# NRF_Breakout.net
KiCad netlist of a schematic drawn in EAGLE
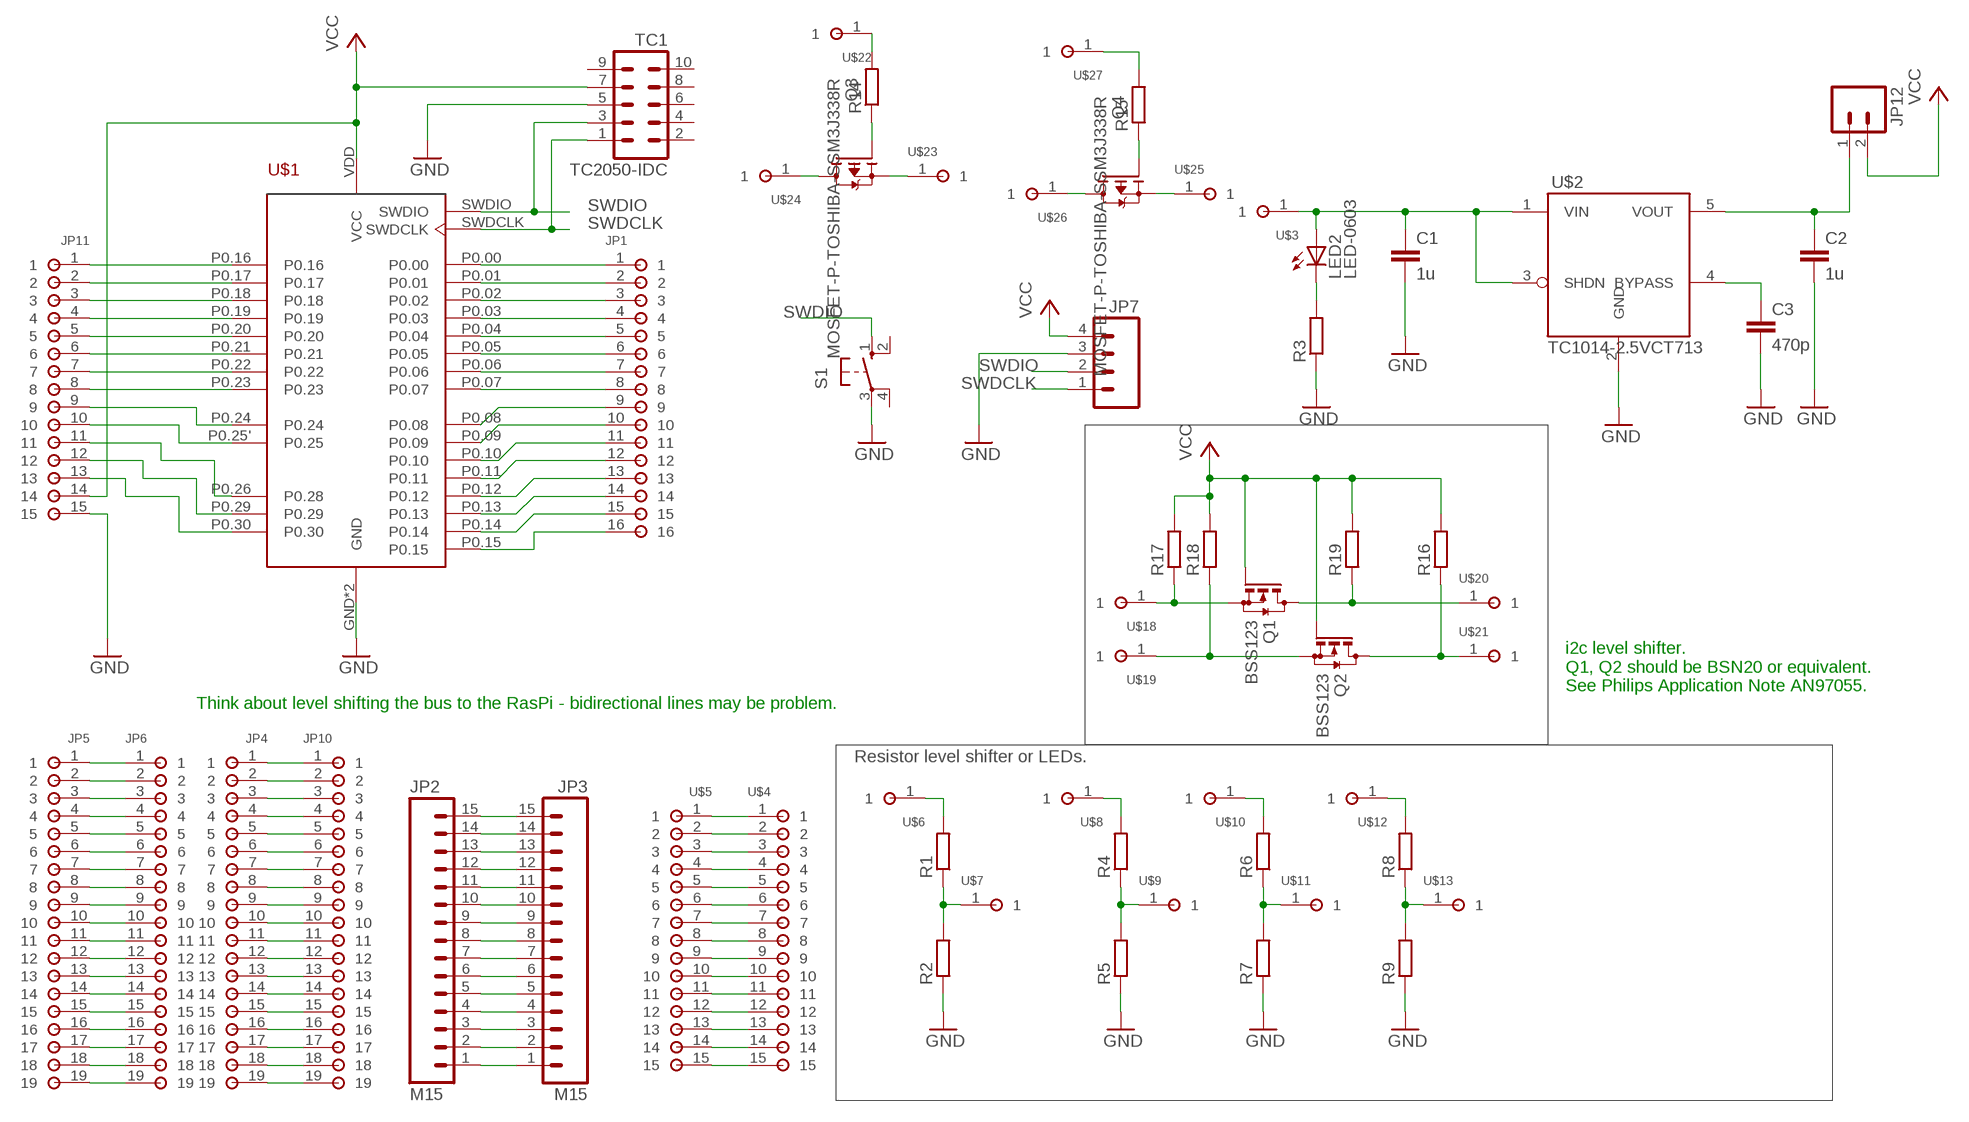
[diagram p0: schematic, sheet 1]

(export (version "E")
  (design (tool "Eeschema 10.0.6"))
  (components
    (comp (ref "C1")
      (value "1u")
      (footprint "eagle-import:C0603")
      (libsource (lib "eagle-import") (part "C-EUC0603"))
    )
    (comp (ref "C2")
      (value "1u")
      (footprint "eagle-import:C0603")
      (libsource (lib "eagle-import") (part "C-EUC0603"))
    )
    (comp (ref "C3")
      (value "470p")
      (footprint "eagle-import:C0603")
      (libsource (lib "eagle-import") (part "C-EUC0603"))
    )
    (comp (ref "JP1")
      (value "PAD-16-TH")
      (footprint "eagle-import:PAD-16-TH")
      (libsource (lib "eagle-import") (part "PAD-16-TH"))
    )
    (comp (ref "JP2")
      (value "M15")
      (footprint "eagle-import:1X15")
      (libsource (lib "eagle-import") (part "M15"))
    )
    (comp (ref "JP3")
      (value "M15")
      (footprint "eagle-import:1X15")
      (libsource (lib "eagle-import") (part "M15"))
    )
    (comp (ref "JP4")
      (value "PAD-19-2.54-TH")
      (footprint "eagle-import:PAD-19-2.54-TH")
      (libsource (lib "eagle-import") (part "PAD-19-2.54-TH"))
    )
    (comp (ref "JP5")
      (value "PAD-19-2.54-TH")
      (footprint "eagle-import:PAD-19-2.54-TH")
      (libsource (lib "eagle-import") (part "PAD-19-2.54-TH"))
    )
    (comp (ref "JP6")
      (value "PAD-19-2.54-TH")
      (footprint "eagle-import:PAD-19-2.54-TH")
      (libsource (lib "eagle-import") (part "PAD-19-2.54-TH"))
    )
    (comp (ref "JP7")
      (value "M04PTH")
      (footprint "eagle-import:1X04")
      (libsource (lib "eagle-import") (part "M04PTH"))
    )
    (comp (ref "JP10")
      (value "PAD-19-2.54-TH")
      (footprint "eagle-import:PAD-19-2.54-TH")
      (libsource (lib "eagle-import") (part "PAD-19-2.54-TH"))
    )
    (comp (ref "JP11")
      (value "PAD-15")
      (footprint "eagle-import:PAD-15-TH")
      (libsource (lib "eagle-import") (part "PAD-15"))
    )
    (comp (ref "JP12")
      (value "M02PTH")
      (footprint "eagle-import:1X02")
      (libsource (lib "eagle-import") (part "M02PTH"))
    )
    (comp (ref "LED2")
      (value "LED-0603")
      (footprint "eagle-import:CHIPLED_0603")
      (libsource (lib "eagle-import") (part "LED-0603"))
    )
    (comp (ref "Q1")
      (value "BSS123")
      (footprint "eagle-import:SOT23")
      (libsource (lib "eagle-import") (part "BSS123"))
    )
    (comp (ref "Q2")
      (value "BSS123")
      (footprint "eagle-import:SOT23")
      (libsource (lib "eagle-import") (part "BSS123"))
    )
    (comp (ref "Q3")
      (value "MOSFET-P-TOSHIBA-SSM3J338R")
      (footprint "eagle-import:SOT23")
      (libsource (lib "eagle-import") (part "MOSFET-P-TOSHIBA-SSM3J338R"))
    )
    (comp (ref "Q4")
      (value "MOSFET-P-TOSHIBA-SSM3J338R")
      (footprint "eagle-import:SOT23")
      (libsource (lib "eagle-import") (part "MOSFET-P-TOSHIBA-SSM3J338R"))
    )
    (comp (ref "R1")
      (value "R-EU_R0603")
      (footprint "eagle-import:R0603")
      (libsource (lib "eagle-import") (part "R-EU_R0603"))
    )
    (comp (ref "R2")
      (value "R-EU_R0603")
      (footprint "eagle-import:R0603")
      (libsource (lib "eagle-import") (part "R-EU_R0603"))
    )
    (comp (ref "R3")
      (value "R-EU_R0603")
      (footprint "eagle-import:R0603")
      (libsource (lib "eagle-import") (part "R-EU_R0603"))
    )
    (comp (ref "R4")
      (value "R-EU_R0603")
      (footprint "eagle-import:R0603")
      (libsource (lib "eagle-import") (part "R-EU_R0603"))
    )
    (comp (ref "R5")
      (value "R-EU_R0603")
      (footprint "eagle-import:R0603")
      (libsource (lib "eagle-import") (part "R-EU_R0603"))
    )
    (comp (ref "R6")
      (value "R-EU_R0603")
      (footprint "eagle-import:R0603")
      (libsource (lib "eagle-import") (part "R-EU_R0603"))
    )
    (comp (ref "R7")
      (value "R-EU_R0603")
      (footprint "eagle-import:R0603")
      (libsource (lib "eagle-import") (part "R-EU_R0603"))
    )
    (comp (ref "R8")
      (value "R-EU_R0603")
      (footprint "eagle-import:R0603")
      (libsource (lib "eagle-import") (part "R-EU_R0603"))
    )
    (comp (ref "R9")
      (value "R-EU_R0603")
      (footprint "eagle-import:R0603")
      (libsource (lib "eagle-import") (part "R-EU_R0603"))
    )
    (comp (ref "R14")
      (value "R-EU_R0603")
      (footprint "eagle-import:R0603")
      (libsource (lib "eagle-import") (part "R-EU_R0603"))
    )
    (comp (ref "R15")
      (value "R-EU_R0603")
      (footprint "eagle-import:R0603")
      (libsource (lib "eagle-import") (part "R-EU_R0603"))
    )
    (comp (ref "R16")
      (value "R-EU_R0603")
      (footprint "eagle-import:R0603")
      (libsource (lib "eagle-import") (part "R-EU_R0603"))
    )
    (comp (ref "R17")
      (value "R-EU_R0603")
      (footprint "eagle-import:R0603")
      (libsource (lib "eagle-import") (part "R-EU_R0603"))
    )
    (comp (ref "R18")
      (value "R-EU_R0603")
      (footprint "eagle-import:R0603")
      (libsource (lib "eagle-import") (part "R-EU_R0603"))
    )
    (comp (ref "R19")
      (value "R-EU_R0603")
      (footprint "eagle-import:R0603")
      (libsource (lib "eagle-import") (part "R-EU_R0603"))
    )
    (comp (ref "S1")
      (value "TACT-4PIN")
      (footprint "eagle-import:B3F-10XX")
      (fields (field (name "MPN") "B3F-1000"))
      (libsource (lib "eagle-import") (part "TACT-4PIN"))
    )
    (comp (ref "TC1")
      (value "TC2050-IDC")
      (footprint "eagle-import:TC2050-IDC")
      (libsource (lib "eagle-import") (part "TC2050-IDC"))
    )
    (comp (ref "U$1")
      (value "BREAKOUT-NRF51822CORE-SULLINS-NPPN092FFKS-RC")
      (footprint "eagle-import:BREAKOUT-NRF51822-CORE-SULLINS-NPPN092FFKS-RC")
      (libsource (lib "eagle-import") (part "BREAKOUT-NRF51822CORE-SULLINS-NPPN092FFKS-RC"))
    )
    (comp (ref "U$2")
      (value "TC1014-2.5VCT713")
      (footprint "eagle-import:SOT-23-5")
      (libsource (lib "eagle-import") (part "TC1014-2.5VCT713"))
    )
    (comp (ref "U$3")
      (value "PAD-1-TH")
      (footprint "eagle-import:PAD-1-TH")
      (libsource (lib "eagle-import") (part "PAD-1-TH"))
    )
    (comp (ref "U$4")
      (value "PAD-15")
      (footprint "eagle-import:PAD-15-TH")
      (libsource (lib "eagle-import") (part "PAD-15"))
    )
    (comp (ref "U$5")
      (value "PAD-15")
      (footprint "eagle-import:PAD-15-TH")
      (libsource (lib "eagle-import") (part "PAD-15"))
    )
    (comp (ref "U$6")
      (value "PAD-1-TH")
      (footprint "eagle-import:PAD-1-TH")
      (libsource (lib "eagle-import") (part "PAD-1-TH"))
    )
    (comp (ref "U$7")
      (value "PAD-1-TH")
      (footprint "eagle-import:PAD-1-TH")
      (libsource (lib "eagle-import") (part "PAD-1-TH"))
    )
    (comp (ref "U$8")
      (value "PAD-1-TH")
      (footprint "eagle-import:PAD-1-TH")
      (libsource (lib "eagle-import") (part "PAD-1-TH"))
    )
    (comp (ref "U$9")
      (value "PAD-1-TH")
      (footprint "eagle-import:PAD-1-TH")
      (libsource (lib "eagle-import") (part "PAD-1-TH"))
    )
    (comp (ref "U$10")
      (value "PAD-1-TH")
      (footprint "eagle-import:PAD-1-TH")
      (libsource (lib "eagle-import") (part "PAD-1-TH"))
    )
    (comp (ref "U$11")
      (value "PAD-1-TH")
      (footprint "eagle-import:PAD-1-TH")
      (libsource (lib "eagle-import") (part "PAD-1-TH"))
    )
    (comp (ref "U$12")
      (value "PAD-1-TH")
      (footprint "eagle-import:PAD-1-TH")
      (libsource (lib "eagle-import") (part "PAD-1-TH"))
    )
    (comp (ref "U$13")
      (value "PAD-1-TH")
      (footprint "eagle-import:PAD-1-TH")
      (libsource (lib "eagle-import") (part "PAD-1-TH"))
    )
    (comp (ref "U$18")
      (value "PAD-1-TH")
      (footprint "eagle-import:PAD-1-TH")
      (libsource (lib "eagle-import") (part "PAD-1-TH"))
    )
    (comp (ref "U$19")
      (value "PAD-1-TH")
      (footprint "eagle-import:PAD-1-TH")
      (libsource (lib "eagle-import") (part "PAD-1-TH"))
    )
    (comp (ref "U$20")
      (value "PAD-1-TH")
      (footprint "eagle-import:PAD-1-TH")
      (libsource (lib "eagle-import") (part "PAD-1-TH"))
    )
    (comp (ref "U$21")
      (value "PAD-1-TH")
      (footprint "eagle-import:PAD-1-TH")
      (libsource (lib "eagle-import") (part "PAD-1-TH"))
    )
    (comp (ref "U$22")
      (value "PAD-1-TH")
      (footprint "eagle-import:PAD-1-TH")
      (libsource (lib "eagle-import") (part "PAD-1-TH"))
    )
    (comp (ref "U$23")
      (value "PAD-1-TH")
      (footprint "eagle-import:PAD-1-TH")
      (libsource (lib "eagle-import") (part "PAD-1-TH"))
    )
    (comp (ref "U$24")
      (value "PAD-1-TH")
      (footprint "eagle-import:PAD-1-TH")
      (libsource (lib "eagle-import") (part "PAD-1-TH"))
    )
    (comp (ref "U$25")
      (value "PAD-1-TH")
      (footprint "eagle-import:PAD-1-TH")
      (libsource (lib "eagle-import") (part "PAD-1-TH"))
    )
    (comp (ref "U$26")
      (value "PAD-1-TH")
      (footprint "eagle-import:PAD-1-TH")
      (libsource (lib "eagle-import") (part "PAD-1-TH"))
    )
    (comp (ref "U$27")
      (value "PAD-1-TH")
      (footprint "eagle-import:PAD-1-TH")
      (libsource (lib "eagle-import") (part "PAD-1-TH"))
    )
  )
  (nets
    (net (code "1") (name "/SWDCLK") (class "Default")
      (node (ref "JP7") (pin "1") (pinfunction "1_1") (pintype "passive"))
      (node (ref "TC1") (pin "1") (pinfunction "1_1") (pintype "passive"))
      (node (ref "U$1") (pin "SWDCLK") (pinfunction "SWDCLK_SWDCLK") (pintype "bidirectional"))
    )
    (net (code "2") (name "/SWDIO") (class "Default")
      (node (ref "JP7") (pin "2") (pinfunction "2_2") (pintype "passive"))
      (node (ref "S1") (pin "1") (pinfunction "S_1") (pintype "passive"))
      (node (ref "TC1") (pin "3") (pinfunction "3_3") (pintype "passive"))
      (node (ref "U$1") (pin "SWDIO") (pinfunction "SWDIO_SWDIO") (pintype "bidirectional"))
    )
    (net (code "3") (name "GND") (class "Default")
      (node (ref "C1") (pin "2") (pinfunction "2_2") (pintype "passive"))
      (node (ref "C2") (pin "2") (pinfunction "2_2") (pintype "passive"))
      (node (ref "C3") (pin "2") (pinfunction "2_2") (pintype "passive"))
      (node (ref "JP11") (pin "15") (pinfunction "15_15") (pintype "bidirectional"))
      (node (ref "JP7") (pin "3") (pinfunction "3_3") (pintype "passive"))
      (node (ref "R2") (pin "1") (pinfunction "1_1") (pintype "passive"))
      (node (ref "R3") (pin "1") (pinfunction "1_1") (pintype "passive"))
      (node (ref "R5") (pin "1") (pinfunction "1_1") (pintype "passive"))
      (node (ref "R7") (pin "1") (pinfunction "1_1") (pintype "passive"))
      (node (ref "R9") (pin "1") (pinfunction "1_1") (pintype "passive"))
      (node (ref "S1") (pin "3") (pinfunction "P_3") (pintype "passive"))
      (node (ref "TC1") (pin "5") (pinfunction "5_5") (pintype "passive"))
      (node (ref "U$1") (pin "GND") (pinfunction "GND_GND") (pintype "bidirectional"))
      (node (ref "U$1") (pin "GND2") (pinfunction "GND_GND2") (pintype "bidirectional"))
      (node (ref "U$2") (pin "2") (pinfunction "GND_2") (pintype "power_in"))
    )
    (net (code "4") (name "Net-(JP1-Pad1)") (class "Default")
      (node (ref "JP1") (pin "1") (pinfunction "1_1") (pintype "bidirectional"))
      (node (ref "U$1") (pin "P0.00") (pinfunction "P0.00_P0.00") (pintype "bidirectional"))
    )
    (net (code "5") (name "Net-(JP1-Pad2)") (class "Default")
      (node (ref "JP1") (pin "2") (pinfunction "2_2") (pintype "bidirectional"))
      (node (ref "U$1") (pin "P0.01") (pinfunction "P0.01_P0.01") (pintype "bidirectional"))
    )
    (net (code "6") (name "Net-(JP1-Pad3)") (class "Default")
      (node (ref "JP1") (pin "3") (pinfunction "3_3") (pintype "bidirectional"))
      (node (ref "U$1") (pin "P0.02") (pinfunction "P0.02_P0.02") (pintype "bidirectional"))
    )
    (net (code "7") (name "Net-(JP1-Pad4)") (class "Default")
      (node (ref "JP1") (pin "4") (pinfunction "4_4") (pintype "bidirectional"))
      (node (ref "U$1") (pin "P0.03") (pinfunction "P0.03_P0.03") (pintype "bidirectional"))
    )
    (net (code "8") (name "Net-(JP1-Pad5)") (class "Default")
      (node (ref "JP1") (pin "5") (pinfunction "5_5") (pintype "bidirectional"))
      (node (ref "U$1") (pin "P0.04") (pinfunction "P0.04_P0.04") (pintype "bidirectional"))
    )
    (net (code "9") (name "Net-(JP1-Pad6)") (class "Default")
      (node (ref "JP1") (pin "6") (pinfunction "6_6") (pintype "bidirectional"))
      (node (ref "U$1") (pin "P0.05") (pinfunction "P0.05_P0.05") (pintype "bidirectional"))
    )
    (net (code "10") (name "Net-(JP1-Pad7)") (class "Default")
      (node (ref "JP1") (pin "7") (pinfunction "7_7") (pintype "bidirectional"))
      (node (ref "U$1") (pin "P0.06") (pinfunction "P0.06_P0.06") (pintype "bidirectional"))
    )
    (net (code "11") (name "Net-(JP1-Pad8)") (class "Default")
      (node (ref "JP1") (pin "8") (pinfunction "8_8") (pintype "bidirectional"))
      (node (ref "U$1") (pin "P0.07") (pinfunction "P0.07_P0.07") (pintype "bidirectional"))
    )
    (net (code "12") (name "Net-(JP1-Pad9)") (class "Default")
      (node (ref "JP1") (pin "9") (pinfunction "9_9") (pintype "bidirectional"))
      (node (ref "U$1") (pin "P0.08") (pinfunction "P0.08_P0.08") (pintype "bidirectional"))
    )
    (net (code "13") (name "Net-(JP1-Pad10)") (class "Default")
      (node (ref "JP1") (pin "10") (pinfunction "10_10") (pintype "bidirectional"))
      (node (ref "U$1") (pin "P0.09") (pinfunction "P0.09_P0.09") (pintype "bidirectional"))
    )
    (net (code "14") (name "Net-(JP1-Pad11)") (class "Default")
      (node (ref "JP1") (pin "11") (pinfunction "11_11") (pintype "bidirectional"))
      (node (ref "U$1") (pin "P0.10") (pinfunction "P0.10_P0.10") (pintype "bidirectional"))
    )
    (net (code "15") (name "Net-(JP1-Pad12)") (class "Default")
      (node (ref "JP1") (pin "12") (pinfunction "12_12") (pintype "bidirectional"))
      (node (ref "U$1") (pin "P0.11") (pinfunction "P0.11_P0.11") (pintype "bidirectional"))
    )
    (net (code "16") (name "Net-(JP1-Pad13)") (class "Default")
      (node (ref "JP1") (pin "13") (pinfunction "13_13") (pintype "bidirectional"))
      (node (ref "U$1") (pin "P0.12") (pinfunction "P0.12_P0.12") (pintype "bidirectional"))
    )
    (net (code "17") (name "Net-(JP1-Pad14)") (class "Default")
      (node (ref "JP1") (pin "14") (pinfunction "14_14") (pintype "bidirectional"))
      (node (ref "U$1") (pin "P0.13") (pinfunction "P0.13_P0.13") (pintype "bidirectional"))
    )
    (net (code "18") (name "Net-(JP1-Pad15)") (class "Default")
      (node (ref "JP1") (pin "15") (pinfunction "15_15") (pintype "bidirectional"))
      (node (ref "U$1") (pin "P0.14") (pinfunction "P0.14_P0.14") (pintype "bidirectional"))
    )
    (net (code "19") (name "Net-(JP1-Pad16)") (class "Default")
      (node (ref "JP1") (pin "16") (pinfunction "16_16") (pintype "bidirectional"))
      (node (ref "U$1") (pin "P0.15") (pinfunction "P0.15_P0.15") (pintype "bidirectional"))
    )
    (net (code "20") (name "Net-(JP2-Pad1)") (class "Default")
      (node (ref "JP2") (pin "1") (pinfunction "1_1") (pintype "passive"))
      (node (ref "JP3") (pin "1") (pinfunction "1_1") (pintype "passive"))
    )
    (net (code "21") (name "Net-(JP2-Pad2)") (class "Default")
      (node (ref "JP2") (pin "2") (pinfunction "2_2") (pintype "passive"))
      (node (ref "JP3") (pin "2") (pinfunction "2_2") (pintype "passive"))
    )
    (net (code "22") (name "Net-(JP2-Pad3)") (class "Default")
      (node (ref "JP2") (pin "3") (pinfunction "3_3") (pintype "passive"))
      (node (ref "JP3") (pin "3") (pinfunction "3_3") (pintype "passive"))
    )
    (net (code "23") (name "Net-(JP2-Pad4)") (class "Default")
      (node (ref "JP2") (pin "4") (pinfunction "4_4") (pintype "passive"))
      (node (ref "JP3") (pin "4") (pinfunction "4_4") (pintype "passive"))
    )
    (net (code "24") (name "Net-(JP2-Pad5)") (class "Default")
      (node (ref "JP2") (pin "5") (pinfunction "5_5") (pintype "passive"))
      (node (ref "JP3") (pin "5") (pinfunction "5_5") (pintype "passive"))
    )
    (net (code "25") (name "Net-(JP2-Pad6)") (class "Default")
      (node (ref "JP2") (pin "6") (pinfunction "6_6") (pintype "passive"))
      (node (ref "JP3") (pin "6") (pinfunction "6_6") (pintype "passive"))
    )
    (net (code "26") (name "Net-(JP2-Pad7)") (class "Default")
      (node (ref "JP2") (pin "7") (pinfunction "7_7") (pintype "passive"))
      (node (ref "JP3") (pin "7") (pinfunction "7_7") (pintype "passive"))
    )
    (net (code "27") (name "Net-(JP2-Pad8)") (class "Default")
      (node (ref "JP2") (pin "8") (pinfunction "8_8") (pintype "passive"))
      (node (ref "JP3") (pin "8") (pinfunction "8_8") (pintype "passive"))
    )
    (net (code "28") (name "Net-(JP2-Pad9)") (class "Default")
      (node (ref "JP2") (pin "9") (pinfunction "9_9") (pintype "passive"))
      (node (ref "JP3") (pin "9") (pinfunction "9_9") (pintype "passive"))
    )
    (net (code "29") (name "Net-(JP2-Pad10)") (class "Default")
      (node (ref "JP2") (pin "10") (pinfunction "10_10") (pintype "passive"))
      (node (ref "JP3") (pin "10") (pinfunction "10_10") (pintype "passive"))
    )
    (net (code "30") (name "Net-(JP2-Pad11)") (class "Default")
      (node (ref "JP2") (pin "11") (pinfunction "11_11") (pintype "passive"))
      (node (ref "JP3") (pin "11") (pinfunction "11_11") (pintype "passive"))
    )
    (net (code "31") (name "Net-(JP2-Pad12)") (class "Default")
      (node (ref "JP2") (pin "12") (pinfunction "12_12") (pintype "passive"))
      (node (ref "JP3") (pin "12") (pinfunction "12_12") (pintype "passive"))
    )
    (net (code "32") (name "Net-(JP2-Pad13)") (class "Default")
      (node (ref "JP2") (pin "13") (pinfunction "13_13") (pintype "passive"))
      (node (ref "JP3") (pin "13") (pinfunction "13_13") (pintype "passive"))
    )
    (net (code "33") (name "Net-(JP2-Pad14)") (class "Default")
      (node (ref "JP2") (pin "14") (pinfunction "14_14") (pintype "passive"))
      (node (ref "JP3") (pin "14") (pinfunction "14_14") (pintype "passive"))
    )
    (net (code "34") (name "Net-(JP2-Pad15)") (class "Default")
      (node (ref "JP2") (pin "15") (pinfunction "15_15") (pintype "passive"))
      (node (ref "JP3") (pin "15") (pinfunction "15_15") (pintype "passive"))
    )
    (net (code "35") (name "Net-(JP5-Pad1)") (class "Default")
      (node (ref "JP5") (pin "1") (pinfunction "1_1") (pintype "bidirectional"))
      (node (ref "JP6") (pin "1") (pinfunction "1_1") (pintype "bidirectional"))
    )
    (net (code "36") (name "Net-(JP5-Pad2)") (class "Default")
      (node (ref "JP5") (pin "2") (pinfunction "2_2") (pintype "bidirectional"))
      (node (ref "JP6") (pin "2") (pinfunction "2_2") (pintype "bidirectional"))
    )
    (net (code "37") (name "Net-(JP5-Pad3)") (class "Default")
      (node (ref "JP5") (pin "3") (pinfunction "3_3") (pintype "bidirectional"))
      (node (ref "JP6") (pin "3") (pinfunction "3_3") (pintype "bidirectional"))
    )
    (net (code "38") (name "Net-(JP5-Pad4)") (class "Default")
      (node (ref "JP5") (pin "4") (pinfunction "4_4") (pintype "bidirectional"))
      (node (ref "JP6") (pin "4") (pinfunction "4_4") (pintype "bidirectional"))
    )
    (net (code "39") (name "Net-(JP5-Pad5)") (class "Default")
      (node (ref "JP5") (pin "5") (pinfunction "5_5") (pintype "bidirectional"))
      (node (ref "JP6") (pin "5") (pinfunction "5_5") (pintype "bidirectional"))
    )
    (net (code "40") (name "Net-(JP5-Pad6)") (class "Default")
      (node (ref "JP5") (pin "6") (pinfunction "6_6") (pintype "bidirectional"))
      (node (ref "JP6") (pin "6") (pinfunction "6_6") (pintype "bidirectional"))
    )
    (net (code "41") (name "Net-(JP5-Pad7)") (class "Default")
      (node (ref "JP5") (pin "7") (pinfunction "7_7") (pintype "bidirectional"))
      (node (ref "JP6") (pin "7") (pinfunction "7_7") (pintype "bidirectional"))
    )
    (net (code "42") (name "Net-(JP5-Pad8)") (class "Default")
      (node (ref "JP5") (pin "8") (pinfunction "8_8") (pintype "bidirectional"))
      (node (ref "JP6") (pin "8") (pinfunction "8_8") (pintype "bidirectional"))
    )
    (net (code "43") (name "Net-(JP5-Pad9)") (class "Default")
      (node (ref "JP5") (pin "9") (pinfunction "9_9") (pintype "bidirectional"))
      (node (ref "JP6") (pin "9") (pinfunction "9_9") (pintype "bidirectional"))
    )
    (net (code "44") (name "Net-(JP5-Pad10)") (class "Default")
      (node (ref "JP5") (pin "10") (pinfunction "10_10") (pintype "bidirectional"))
      (node (ref "JP6") (pin "10") (pinfunction "10_10") (pintype "bidirectional"))
    )
    (net (code "45") (name "Net-(JP5-Pad11)") (class "Default")
      (node (ref "JP5") (pin "11") (pinfunction "11_11") (pintype "bidirectional"))
      (node (ref "JP6") (pin "11") (pinfunction "11_11") (pintype "bidirectional"))
    )
    (net (code "46") (name "Net-(JP5-Pad12)") (class "Default")
      (node (ref "JP5") (pin "12") (pinfunction "12_12") (pintype "bidirectional"))
      (node (ref "JP6") (pin "12") (pinfunction "12_12") (pintype "bidirectional"))
    )
    (net (code "47") (name "Net-(JP5-Pad13)") (class "Default")
      (node (ref "JP5") (pin "13") (pinfunction "13_13") (pintype "bidirectional"))
      (node (ref "JP6") (pin "13") (pinfunction "13_13") (pintype "bidirectional"))
    )
    (net (code "48") (name "Net-(JP5-Pad14)") (class "Default")
      (node (ref "JP5") (pin "14") (pinfunction "14_14") (pintype "bidirectional"))
      (node (ref "JP6") (pin "14") (pinfunction "14_14") (pintype "bidirectional"))
    )
    (net (code "49") (name "Net-(JP5-Pad15)") (class "Default")
      (node (ref "JP5") (pin "15") (pinfunction "15_15") (pintype "bidirectional"))
      (node (ref "JP6") (pin "15") (pinfunction "15_15") (pintype "bidirectional"))
    )
    (net (code "50") (name "Net-(JP5-Pad16)") (class "Default")
      (node (ref "JP5") (pin "16") (pinfunction "16_16") (pintype "bidirectional"))
      (node (ref "JP6") (pin "16") (pinfunction "16_16") (pintype "bidirectional"))
    )
    (net (code "51") (name "Net-(JP5-Pad17)") (class "Default")
      (node (ref "JP5") (pin "17") (pinfunction "17_17") (pintype "bidirectional"))
      (node (ref "JP6") (pin "17") (pinfunction "17_17") (pintype "bidirectional"))
    )
    (net (code "52") (name "Net-(JP5-Pad18)") (class "Default")
      (node (ref "JP5") (pin "18") (pinfunction "18_18") (pintype "bidirectional"))
      (node (ref "JP6") (pin "18") (pinfunction "18_18") (pintype "bidirectional"))
    )
    (net (code "53") (name "Net-(JP5-Pad19)") (class "Default")
      (node (ref "JP5") (pin "19") (pinfunction "19_19") (pintype "bidirectional"))
      (node (ref "JP6") (pin "19") (pinfunction "19_19") (pintype "bidirectional"))
    )
    (net (code "54") (name "Net-(JP10-Pad1)") (class "Default")
      (node (ref "JP10") (pin "1") (pinfunction "1_1") (pintype "bidirectional"))
      (node (ref "JP4") (pin "1") (pinfunction "1_1") (pintype "bidirectional"))
    )
    (net (code "55") (name "Net-(JP10-Pad2)") (class "Default")
      (node (ref "JP10") (pin "2") (pinfunction "2_2") (pintype "bidirectional"))
      (node (ref "JP4") (pin "2") (pinfunction "2_2") (pintype "bidirectional"))
    )
    (net (code "56") (name "Net-(JP10-Pad3)") (class "Default")
      (node (ref "JP10") (pin "3") (pinfunction "3_3") (pintype "bidirectional"))
      (node (ref "JP4") (pin "3") (pinfunction "3_3") (pintype "bidirectional"))
    )
    (net (code "57") (name "Net-(JP10-Pad4)") (class "Default")
      (node (ref "JP10") (pin "4") (pinfunction "4_4") (pintype "bidirectional"))
      (node (ref "JP4") (pin "4") (pinfunction "4_4") (pintype "bidirectional"))
    )
    (net (code "58") (name "Net-(JP10-Pad5)") (class "Default")
      (node (ref "JP10") (pin "5") (pinfunction "5_5") (pintype "bidirectional"))
      (node (ref "JP4") (pin "5") (pinfunction "5_5") (pintype "bidirectional"))
    )
    (net (code "59") (name "Net-(JP10-Pad6)") (class "Default")
      (node (ref "JP10") (pin "6") (pinfunction "6_6") (pintype "bidirectional"))
      (node (ref "JP4") (pin "6") (pinfunction "6_6") (pintype "bidirectional"))
    )
    (net (code "60") (name "Net-(JP10-Pad7)") (class "Default")
      (node (ref "JP10") (pin "7") (pinfunction "7_7") (pintype "bidirectional"))
      (node (ref "JP4") (pin "7") (pinfunction "7_7") (pintype "bidirectional"))
    )
    (net (code "61") (name "Net-(JP10-Pad8)") (class "Default")
      (node (ref "JP10") (pin "8") (pinfunction "8_8") (pintype "bidirectional"))
      (node (ref "JP4") (pin "8") (pinfunction "8_8") (pintype "bidirectional"))
    )
    (net (code "62") (name "Net-(JP10-Pad9)") (class "Default")
      (node (ref "JP10") (pin "9") (pinfunction "9_9") (pintype "bidirectional"))
      (node (ref "JP4") (pin "9") (pinfunction "9_9") (pintype "bidirectional"))
    )
    (net (code "63") (name "Net-(JP10-Pad10)") (class "Default")
      (node (ref "JP10") (pin "10") (pinfunction "10_10") (pintype "bidirectional"))
      (node (ref "JP4") (pin "10") (pinfunction "10_10") (pintype "bidirectional"))
    )
    (net (code "64") (name "Net-(JP10-Pad11)") (class "Default")
      (node (ref "JP10") (pin "11") (pinfunction "11_11") (pintype "bidirectional"))
      (node (ref "JP4") (pin "11") (pinfunction "11_11") (pintype "bidirectional"))
    )
    (net (code "65") (name "Net-(JP10-Pad12)") (class "Default")
      (node (ref "JP10") (pin "12") (pinfunction "12_12") (pintype "bidirectional"))
      (node (ref "JP4") (pin "12") (pinfunction "12_12") (pintype "bidirectional"))
    )
    (net (code "66") (name "Net-(JP10-Pad13)") (class "Default")
      (node (ref "JP10") (pin "13") (pinfunction "13_13") (pintype "bidirectional"))
      (node (ref "JP4") (pin "13") (pinfunction "13_13") (pintype "bidirectional"))
    )
    (net (code "67") (name "Net-(JP10-Pad14)") (class "Default")
      (node (ref "JP10") (pin "14") (pinfunction "14_14") (pintype "bidirectional"))
      (node (ref "JP4") (pin "14") (pinfunction "14_14") (pintype "bidirectional"))
    )
    (net (code "68") (name "Net-(JP10-Pad15)") (class "Default")
      (node (ref "JP10") (pin "15") (pinfunction "15_15") (pintype "bidirectional"))
      (node (ref "JP4") (pin "15") (pinfunction "15_15") (pintype "bidirectional"))
    )
    (net (code "69") (name "Net-(JP10-Pad16)") (class "Default")
      (node (ref "JP10") (pin "16") (pinfunction "16_16") (pintype "bidirectional"))
      (node (ref "JP4") (pin "16") (pinfunction "16_16") (pintype "bidirectional"))
    )
    (net (code "70") (name "Net-(JP10-Pad17)") (class "Default")
      (node (ref "JP10") (pin "17") (pinfunction "17_17") (pintype "bidirectional"))
      (node (ref "JP4") (pin "17") (pinfunction "17_17") (pintype "bidirectional"))
    )
    (net (code "71") (name "Net-(JP10-Pad18)") (class "Default")
      (node (ref "JP10") (pin "18") (pinfunction "18_18") (pintype "bidirectional"))
      (node (ref "JP4") (pin "18") (pinfunction "18_18") (pintype "bidirectional"))
    )
    (net (code "72") (name "Net-(JP10-Pad19)") (class "Default")
      (node (ref "JP10") (pin "19") (pinfunction "19_19") (pintype "bidirectional"))
      (node (ref "JP4") (pin "19") (pinfunction "19_19") (pintype "bidirectional"))
    )
    (net (code "73") (name "Net-(JP11-Pad1)") (class "Default")
      (node (ref "JP11") (pin "1") (pinfunction "1_1") (pintype "bidirectional"))
      (node (ref "U$1") (pin "P0.16") (pinfunction "P0.16_P0.16") (pintype "bidirectional"))
    )
    (net (code "74") (name "Net-(JP11-Pad2)") (class "Default")
      (node (ref "JP11") (pin "2") (pinfunction "2_2") (pintype "bidirectional"))
      (node (ref "U$1") (pin "P0.17") (pinfunction "P0.17_P0.17") (pintype "bidirectional"))
    )
    (net (code "75") (name "Net-(JP11-Pad3)") (class "Default")
      (node (ref "JP11") (pin "3") (pinfunction "3_3") (pintype "bidirectional"))
      (node (ref "U$1") (pin "P0.18") (pinfunction "P0.18_P0.18") (pintype "bidirectional"))
    )
    (net (code "76") (name "Net-(JP11-Pad4)") (class "Default")
      (node (ref "JP11") (pin "4") (pinfunction "4_4") (pintype "bidirectional"))
      (node (ref "U$1") (pin "P0.19") (pinfunction "P0.19_P0.19") (pintype "bidirectional"))
    )
    (net (code "77") (name "Net-(JP11-Pad5)") (class "Default")
      (node (ref "JP11") (pin "5") (pinfunction "5_5") (pintype "bidirectional"))
      (node (ref "U$1") (pin "P0.20") (pinfunction "P0.20_P0.20") (pintype "bidirectional"))
    )
    (net (code "78") (name "Net-(JP11-Pad6)") (class "Default")
      (node (ref "JP11") (pin "6") (pinfunction "6_6") (pintype "bidirectional"))
      (node (ref "U$1") (pin "P0.21") (pinfunction "P0.21_P0.21") (pintype "bidirectional"))
    )
    (net (code "79") (name "Net-(JP11-Pad7)") (class "Default")
      (node (ref "JP11") (pin "7") (pinfunction "7_7") (pintype "bidirectional"))
      (node (ref "U$1") (pin "P0.22") (pinfunction "P0.22_P0.22") (pintype "bidirectional"))
    )
    (net (code "80") (name "Net-(JP11-Pad8)") (class "Default")
      (node (ref "JP11") (pin "8") (pinfunction "8_8") (pintype "bidirectional"))
      (node (ref "U$1") (pin "P0.23") (pinfunction "P0.23_P0.23") (pintype "bidirectional"))
    )
    (net (code "81") (name "Net-(JP11-Pad9)") (class "Default")
      (node (ref "JP11") (pin "9") (pinfunction "9_9") (pintype "bidirectional"))
      (node (ref "U$1") (pin "P0.24") (pinfunction "P0.24_P0.24") (pintype "bidirectional"))
    )
    (net (code "82") (name "Net-(JP11-Pad12)") (class "Default")
      (node (ref "JP11") (pin "12") (pinfunction "12_12") (pintype "bidirectional"))
      (node (ref "U$1") (pin "P0.29") (pinfunction "P0.29_P0.29") (pintype "bidirectional"))
    )
    (net (code "83") (name "Net-(JP11-Pad13)") (class "Default")
      (node (ref "JP11") (pin "13") (pinfunction "13_13") (pintype "bidirectional"))
      (node (ref "U$1") (pin "P0.30") (pinfunction "P0.30_P0.30") (pintype "bidirectional"))
    )
    (net (code "84") (name "Net-(LED2-PadC)") (class "Default")
      (node (ref "LED2") (pin "C") (pinfunction "C_C") (pintype "passive"))
      (node (ref "R3") (pin "2") (pinfunction "2_2") (pintype "passive"))
    )
    (net (code "85") (name "Net-(Q1-D)") (class "Default")
      (node (ref "Q1") (pin "3") (pinfunction "D_3") (pintype "passive"))
      (node (ref "R19") (pin "1") (pinfunction "1_1") (pintype "passive"))
      (node (ref "U$20") (pin "1") (pinfunction "1_1") (pintype "bidirectional"))
    )
    (net (code "86") (name "Net-(Q1-S)") (class "Default")
      (node (ref "Q1") (pin "2") (pinfunction "S_2") (pintype "passive"))
      (node (ref "R17") (pin "1") (pinfunction "1_1") (pintype "passive"))
      (node (ref "U$18") (pin "1") (pinfunction "1_1") (pintype "bidirectional"))
    )
    (net (code "87") (name "Net-(Q2-D)") (class "Default")
      (node (ref "Q2") (pin "3") (pinfunction "D_3") (pintype "passive"))
      (node (ref "R16") (pin "1") (pinfunction "1_1") (pintype "passive"))
      (node (ref "U$21") (pin "1") (pinfunction "1_1") (pintype "bidirectional"))
    )
    (net (code "88") (name "Net-(Q2-S)") (class "Default")
      (node (ref "Q2") (pin "2") (pinfunction "S_2") (pintype "passive"))
      (node (ref "R18") (pin "1") (pinfunction "1_1") (pintype "passive"))
      (node (ref "U$19") (pin "1") (pinfunction "1_1") (pintype "bidirectional"))
    )
    (net (code "89") (name "Net-(Q3-D)") (class "Default")
      (node (ref "Q3") (pin "3") (pinfunction "D_3") (pintype "passive"))
      (node (ref "U$24") (pin "1") (pinfunction "1_1") (pintype "bidirectional"))
    )
    (net (code "90") (name "Net-(Q3-G)") (class "Default")
      (node (ref "Q3") (pin "1") (pinfunction "G_1") (pintype "passive"))
      (node (ref "R14") (pin "1") (pinfunction "1_1") (pintype "passive"))
    )
    (net (code "91") (name "Net-(Q3-S)") (class "Default")
      (node (ref "Q3") (pin "2") (pinfunction "S_2") (pintype "passive"))
      (node (ref "U$23") (pin "1") (pinfunction "1_1") (pintype "bidirectional"))
    )
    (net (code "92") (name "Net-(Q4-D)") (class "Default")
      (node (ref "Q4") (pin "3") (pinfunction "D_3") (pintype "passive"))
      (node (ref "U$26") (pin "1") (pinfunction "1_1") (pintype "bidirectional"))
    )
    (net (code "93") (name "Net-(Q4-G)") (class "Default")
      (node (ref "Q4") (pin "1") (pinfunction "G_1") (pintype "passive"))
      (node (ref "R15") (pin "1") (pinfunction "1_1") (pintype "passive"))
    )
    (net (code "94") (name "Net-(Q4-S)") (class "Default")
      (node (ref "Q4") (pin "2") (pinfunction "S_2") (pintype "passive"))
      (node (ref "U$25") (pin "1") (pinfunction "1_1") (pintype "bidirectional"))
    )
    (net (code "95") (name "Net-(R1-Pad1)") (class "Default")
      (node (ref "R1") (pin "1") (pinfunction "1_1") (pintype "passive"))
      (node (ref "R2") (pin "2") (pinfunction "2_2") (pintype "passive"))
      (node (ref "U$7") (pin "1") (pinfunction "1_1") (pintype "bidirectional"))
    )
    (net (code "96") (name "Net-(R1-Pad2)") (class "Default")
      (node (ref "R1") (pin "2") (pinfunction "2_2") (pintype "passive"))
      (node (ref "U$6") (pin "1") (pinfunction "1_1") (pintype "bidirectional"))
    )
    (net (code "97") (name "Net-(R4-Pad1)") (class "Default")
      (node (ref "R4") (pin "1") (pinfunction "1_1") (pintype "passive"))
      (node (ref "R5") (pin "2") (pinfunction "2_2") (pintype "passive"))
      (node (ref "U$9") (pin "1") (pinfunction "1_1") (pintype "bidirectional"))
    )
    (net (code "98") (name "Net-(R4-Pad2)") (class "Default")
      (node (ref "R4") (pin "2") (pinfunction "2_2") (pintype "passive"))
      (node (ref "U$8") (pin "1") (pinfunction "1_1") (pintype "bidirectional"))
    )
    (net (code "99") (name "Net-(R6-Pad1)") (class "Default")
      (node (ref "R6") (pin "1") (pinfunction "1_1") (pintype "passive"))
      (node (ref "R7") (pin "2") (pinfunction "2_2") (pintype "passive"))
      (node (ref "U$11") (pin "1") (pinfunction "1_1") (pintype "bidirectional"))
    )
    (net (code "100") (name "Net-(R6-Pad2)") (class "Default")
      (node (ref "R6") (pin "2") (pinfunction "2_2") (pintype "passive"))
      (node (ref "U$10") (pin "1") (pinfunction "1_1") (pintype "bidirectional"))
    )
    (net (code "101") (name "Net-(R8-Pad1)") (class "Default")
      (node (ref "R8") (pin "1") (pinfunction "1_1") (pintype "passive"))
      (node (ref "R9") (pin "2") (pinfunction "2_2") (pintype "passive"))
      (node (ref "U$13") (pin "1") (pinfunction "1_1") (pintype "bidirectional"))
    )
    (net (code "102") (name "Net-(R8-Pad2)") (class "Default")
      (node (ref "R8") (pin "2") (pinfunction "2_2") (pintype "passive"))
      (node (ref "U$12") (pin "1") (pinfunction "1_1") (pintype "bidirectional"))
    )
    (net (code "103") (name "Net-(R14-Pad2)") (class "Default")
      (node (ref "R14") (pin "2") (pinfunction "2_2") (pintype "passive"))
      (node (ref "U$22") (pin "1") (pinfunction "1_1") (pintype "bidirectional"))
    )
    (net (code "104") (name "Net-(R15-Pad2)") (class "Default")
      (node (ref "R15") (pin "2") (pinfunction "2_2") (pintype "passive"))
      (node (ref "U$27") (pin "1") (pinfunction "1_1") (pintype "bidirectional"))
    )
    (net (code "105") (name "Net-(U$1-P0.25)") (class "Default")
      (node (ref "JP11") (pin "10") (pinfunction "10_10") (pintype "bidirectional"))
      (node (ref "U$1") (pin "P0.25'") (pinfunction "P0.25_P0.25'") (pintype "bidirectional"))
    )
    (net (code "106") (name "Net-(U$1-P0.28)") (class "Default")
      (node (ref "JP11") (pin "11") (pinfunction "11_11") (pintype "bidirectional"))
      (node (ref "U$1") (pin "P0.26") (pinfunction "P0.28_P0.26") (pintype "bidirectional"))
    )
    (net (code "107") (name "Net-(U$2-BYPASS)") (class "Default")
      (node (ref "C3") (pin "1") (pinfunction "1_1") (pintype "passive"))
      (node (ref "U$2") (pin "4") (pinfunction "BYPASS_4") (pintype "passive"))
    )
    (net (code "108") (name "Net-(U$2-SHDN)") (class "Default")
      (node (ref "C1") (pin "1") (pinfunction "1_1") (pintype "passive"))
      (node (ref "LED2") (pin "A") (pinfunction "A_A") (pintype "passive"))
      (node (ref "U$2") (pin "1") (pinfunction "VIN_1") (pintype "power_in"))
      (node (ref "U$2") (pin "3") (pinfunction "SHDN_3") (pintype "input"))
      (node (ref "U$3") (pin "1") (pinfunction "1_1") (pintype "bidirectional"))
    )
    (net (code "109") (name "Net-(U$2-VOUT)") (class "Default")
      (node (ref "C2") (pin "1") (pinfunction "1_1") (pintype "passive"))
      (node (ref "JP12") (pin "1") (pinfunction "1_1") (pintype "passive"))
      (node (ref "U$2") (pin "5") (pinfunction "VOUT_5") (pintype "power_in"))
    )
    (net (code "110") (name "Net-(U$4-Pad1)") (class "Default")
      (node (ref "U$4") (pin "1") (pinfunction "1_1") (pintype "bidirectional"))
      (node (ref "U$5") (pin "1") (pinfunction "1_1") (pintype "bidirectional"))
    )
    (net (code "111") (name "Net-(U$4-Pad2)") (class "Default")
      (node (ref "U$4") (pin "2") (pinfunction "2_2") (pintype "bidirectional"))
      (node (ref "U$5") (pin "2") (pinfunction "2_2") (pintype "bidirectional"))
    )
    (net (code "112") (name "Net-(U$4-Pad3)") (class "Default")
      (node (ref "U$4") (pin "3") (pinfunction "3_3") (pintype "bidirectional"))
      (node (ref "U$5") (pin "3") (pinfunction "3_3") (pintype "bidirectional"))
    )
    (net (code "113") (name "Net-(U$4-Pad4)") (class "Default")
      (node (ref "U$4") (pin "4") (pinfunction "4_4") (pintype "bidirectional"))
      (node (ref "U$5") (pin "4") (pinfunction "4_4") (pintype "bidirectional"))
    )
    (net (code "114") (name "Net-(U$4-Pad5)") (class "Default")
      (node (ref "U$4") (pin "5") (pinfunction "5_5") (pintype "bidirectional"))
      (node (ref "U$5") (pin "5") (pinfunction "5_5") (pintype "bidirectional"))
    )
    (net (code "115") (name "Net-(U$4-Pad6)") (class "Default")
      (node (ref "U$4") (pin "6") (pinfunction "6_6") (pintype "bidirectional"))
      (node (ref "U$5") (pin "6") (pinfunction "6_6") (pintype "bidirectional"))
    )
    (net (code "116") (name "Net-(U$4-Pad7)") (class "Default")
      (node (ref "U$4") (pin "7") (pinfunction "7_7") (pintype "bidirectional"))
      (node (ref "U$5") (pin "7") (pinfunction "7_7") (pintype "bidirectional"))
    )
    (net (code "117") (name "Net-(U$4-Pad8)") (class "Default")
      (node (ref "U$4") (pin "8") (pinfunction "8_8") (pintype "bidirectional"))
      (node (ref "U$5") (pin "8") (pinfunction "8_8") (pintype "bidirectional"))
    )
    (net (code "118") (name "Net-(U$4-Pad9)") (class "Default")
      (node (ref "U$4") (pin "9") (pinfunction "9_9") (pintype "bidirectional"))
      (node (ref "U$5") (pin "9") (pinfunction "9_9") (pintype "bidirectional"))
    )
    (net (code "119") (name "Net-(U$4-Pad10)") (class "Default")
      (node (ref "U$4") (pin "10") (pinfunction "10_10") (pintype "bidirectional"))
      (node (ref "U$5") (pin "10") (pinfunction "10_10") (pintype "bidirectional"))
    )
    (net (code "120") (name "Net-(U$4-Pad11)") (class "Default")
      (node (ref "U$4") (pin "11") (pinfunction "11_11") (pintype "bidirectional"))
      (node (ref "U$5") (pin "11") (pinfunction "11_11") (pintype "bidirectional"))
    )
    (net (code "121") (name "Net-(U$4-Pad12)") (class "Default")
      (node (ref "U$4") (pin "12") (pinfunction "12_12") (pintype "bidirectional"))
      (node (ref "U$5") (pin "12") (pinfunction "12_12") (pintype "bidirectional"))
    )
    (net (code "122") (name "Net-(U$4-Pad13)") (class "Default")
      (node (ref "U$4") (pin "13") (pinfunction "13_13") (pintype "bidirectional"))
      (node (ref "U$5") (pin "13") (pinfunction "13_13") (pintype "bidirectional"))
    )
    (net (code "123") (name "Net-(U$4-Pad14)") (class "Default")
      (node (ref "U$4") (pin "14") (pinfunction "14_14") (pintype "bidirectional"))
      (node (ref "U$5") (pin "14") (pinfunction "14_14") (pintype "bidirectional"))
    )
    (net (code "124") (name "Net-(U$4-Pad15)") (class "Default")
      (node (ref "U$4") (pin "15") (pinfunction "15_15") (pintype "bidirectional"))
      (node (ref "U$5") (pin "15") (pinfunction "15_15") (pintype "bidirectional"))
    )
    (net (code "125") (name "VCC") (class "Default")
      (node (ref "JP11") (pin "14") (pinfunction "14_14") (pintype "bidirectional"))
      (node (ref "JP12") (pin "2") (pinfunction "2_2") (pintype "passive"))
      (node (ref "JP7") (pin "4") (pinfunction "4_4") (pintype "passive"))
      (node (ref "Q1") (pin "1") (pinfunction "G_1") (pintype "passive"))
      (node (ref "Q2") (pin "1") (pinfunction "G_1") (pintype "passive"))
      (node (ref "R16") (pin "2") (pinfunction "2_2") (pintype "passive"))
      (node (ref "R17") (pin "2") (pinfunction "2_2") (pintype "passive"))
      (node (ref "R18") (pin "2") (pinfunction "2_2") (pintype "passive"))
      (node (ref "R19") (pin "2") (pinfunction "2_2") (pintype "passive"))
      (node (ref "TC1") (pin "7") (pinfunction "7_7") (pintype "passive"))
      (node (ref "U$1") (pin "VDD") (pinfunction "VCC_VDD") (pintype "power_in"))
    )
    (net (code "126") (name "unconnected-(S1-P1-Pad4)") (class "Default")
      (node (ref "S1") (pin "4") (pinfunction "P1_4") (pintype "passive"))
    )
    (net (code "127") (name "unconnected-(S1-S1-Pad2)") (class "Default")
      (node (ref "S1") (pin "2") (pinfunction "S1_2") (pintype "passive"))
    )
    (net (code "128") (name "unconnected-(TC1-Pad2)") (class "Default")
      (node (ref "TC1") (pin "2") (pinfunction "2_2") (pintype "passive"))
    )
    (net (code "129") (name "unconnected-(TC1-Pad4)") (class "Default")
      (node (ref "TC1") (pin "4") (pinfunction "4_4") (pintype "passive"))
    )
    (net (code "130") (name "unconnected-(TC1-Pad6)") (class "Default")
      (node (ref "TC1") (pin "6") (pinfunction "6_6") (pintype "passive"))
    )
    (net (code "131") (name "unconnected-(TC1-Pad8)") (class "Default")
      (node (ref "TC1") (pin "8") (pinfunction "8_8") (pintype "passive"))
    )
    (net (code "132") (name "unconnected-(TC1-Pad9)") (class "Default")
      (node (ref "TC1") (pin "9") (pinfunction "9_9") (pintype "passive"))
    )
    (net (code "133") (name "unconnected-(TC1-Pad10)") (class "Default")
      (node (ref "TC1") (pin "10") (pinfunction "10_10") (pintype "passive"))
    )
  )
)
